# micromouse.net
KiCad netlist of a schematic drawn in EAGLE
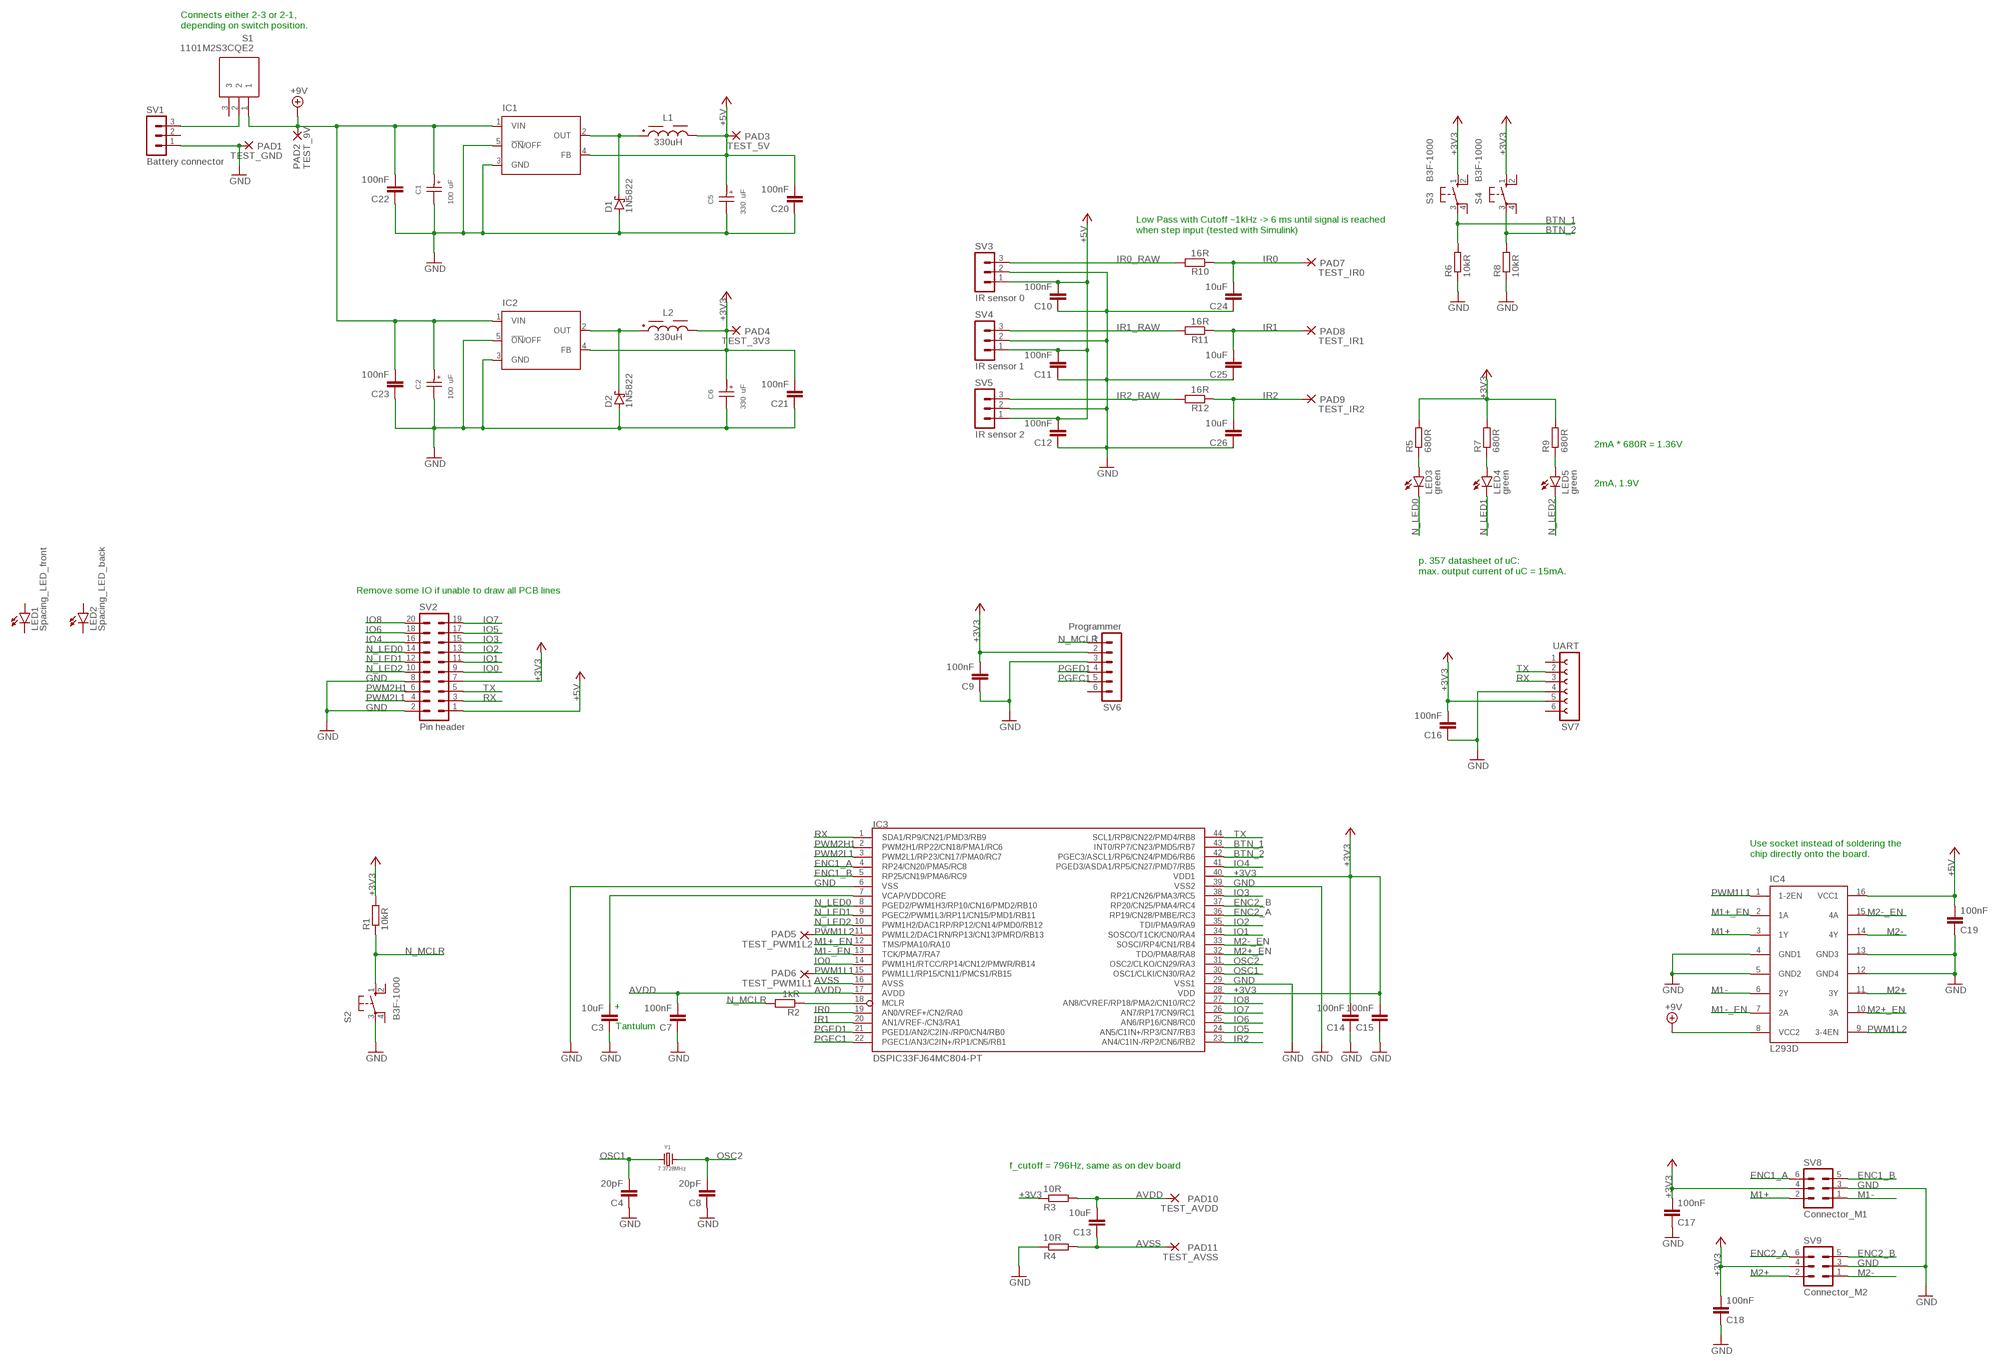
[diagram p0: schematic, sheet 1]

(export (version "E")
  (design (tool "Eeschema 10.0.6"))
  (components
    (comp (ref "C1")
      (value "100 uF")
      (footprint "eagle-import:WCAP-ATG5_5X11(DXL)")
      (libsource (lib "eagle-import") (part "WCAP-ATG5_5X11_860020272005"))
    )
    (comp (ref "C2")
      (value "100 uF")
      (footprint "eagle-import:WCAP-ATG5_5X11(DXL)")
      (libsource (lib "eagle-import") (part "WCAP-ATG5_5X11_860020272005"))
    )
    (comp (ref "C3")
      (value "10uF")
      (footprint "eagle-import:C0805")
      (libsource (lib "eagle-import") (part "C-EUC0805"))
    )
    (comp (ref "C4")
      (value "20pF")
      (footprint "eagle-import:C0805")
      (libsource (lib "eagle-import") (part "C-EUC0805"))
    )
    (comp (ref "C5")
      (value "330 uF")
      (footprint "eagle-import:WCAP-ATG5_6.3X11(DXL)")
      (libsource (lib "eagle-import") (part "WCAP-ATG5_6.3X11_860020273010"))
    )
    (comp (ref "C6")
      (value "330 uF")
      (footprint "eagle-import:WCAP-ATG5_6.3X11(DXL)")
      (libsource (lib "eagle-import") (part "WCAP-ATG5_6.3X11_860020273010"))
    )
    (comp (ref "C7")
      (value "100nF")
      (footprint "eagle-import:C0805")
      (libsource (lib "eagle-import") (part "C-EUC0805"))
    )
    (comp (ref "C8")
      (value "20pF")
      (footprint "eagle-import:C0805")
      (libsource (lib "eagle-import") (part "C-EUC0805"))
    )
    (comp (ref "C9")
      (value "100nF")
      (footprint "eagle-import:C0805")
      (libsource (lib "eagle-import") (part "C-EUC0805"))
    )
    (comp (ref "C10")
      (value "100nF")
      (footprint "eagle-import:C0805")
      (libsource (lib "eagle-import") (part "C-EUC0805"))
    )
    (comp (ref "C11")
      (value "100nF")
      (footprint "eagle-import:C0805")
      (libsource (lib "eagle-import") (part "C-EUC0805"))
    )
    (comp (ref "C12")
      (value "100nF")
      (footprint "eagle-import:C0805")
      (libsource (lib "eagle-import") (part "C-EUC0805"))
    )
    (comp (ref "C13")
      (value "10uF")
      (footprint "eagle-import:C0805")
      (libsource (lib "eagle-import") (part "C-EUC0805"))
    )
    (comp (ref "C14")
      (value "100nF")
      (footprint "eagle-import:C0805")
      (libsource (lib "eagle-import") (part "C-EUC0805"))
    )
    (comp (ref "C15")
      (value "100nF")
      (footprint "eagle-import:C0805")
      (libsource (lib "eagle-import") (part "C-EUC0805"))
    )
    (comp (ref "C16")
      (value "100nF")
      (footprint "eagle-import:C0805")
      (libsource (lib "eagle-import") (part "C-EUC0805"))
    )
    (comp (ref "C17")
      (value "100nF")
      (footprint "eagle-import:C0805")
      (libsource (lib "eagle-import") (part "C-EUC0805"))
    )
    (comp (ref "C18")
      (value "100nF")
      (footprint "eagle-import:C0805")
      (libsource (lib "eagle-import") (part "C-EUC0805"))
    )
    (comp (ref "C19")
      (value "100nF")
      (footprint "eagle-import:C0805")
      (libsource (lib "eagle-import") (part "C-EUC0805"))
    )
    (comp (ref "C20")
      (value "100nF")
      (footprint "eagle-import:C0805")
      (libsource (lib "eagle-import") (part "C-EUC0805"))
    )
    (comp (ref "C21")
      (value "100nF")
      (footprint "eagle-import:C0805")
      (libsource (lib "eagle-import") (part "C-EUC0805"))
    )
    (comp (ref "C22")
      (value "100nF")
      (footprint "eagle-import:C0805")
      (libsource (lib "eagle-import") (part "C-EUC0805"))
    )
    (comp (ref "C23")
      (value "100nF")
      (footprint "eagle-import:C0805")
      (libsource (lib "eagle-import") (part "C-EUC0805"))
    )
    (comp (ref "C24")
      (value "10uF")
      (footprint "eagle-import:C0805")
      (libsource (lib "eagle-import") (part "C-EUC0805"))
    )
    (comp (ref "C25")
      (value "10uF")
      (footprint "eagle-import:C0805")
      (libsource (lib "eagle-import") (part "C-EUC0805"))
    )
    (comp (ref "C26")
      (value "10uF")
      (footprint "eagle-import:C0805")
      (libsource (lib "eagle-import") (part "C-EUC0805"))
    )
    (comp (ref "D1")
      (value "1N5822")
      (footprint "eagle-import:DO35-10")
      (libsource (lib "eagle-import") (part "BAT19"))
    )
    (comp (ref "D2")
      (value "1N5822")
      (footprint "eagle-import:DO35-10")
      (libsource (lib "eagle-import") (part "BAT19"))
    )
    (comp (ref "IC1")
      (value "LM2575-5.0WU-(TR)")
      (footprint "eagle-import:TO263-5")
      (fields (field (name "MF") "NATIONAL SEMICONDUCTOR") (field (name "MPN") "LM2596S-ADJ/NOPB"))
      (libsource (lib "eagle-import") (part "LM2596S"))
    )
    (comp (ref "IC2")
      (value "LM2575-3.3WU-(TR)")
      (footprint "eagle-import:TO263-5")
      (fields (field (name "MF") "NATIONAL SEMICONDUCTOR") (field (name "MPN") "LM2596S-ADJ/NOPB"))
      (libsource (lib "eagle-import") (part "LM2596S"))
    )
    (comp (ref "IC3")
      (value "DSPIC33FJ64MC804-PT")
      (footprint "eagle-import:TQFP44")
      (libsource (lib "eagle-import") (part "DSPIC33FJ64MC804-PT"))
    )
    (comp (ref "IC4")
      (value "L293D")
      (footprint "eagle-import:DIL16")
      (libsource (lib "eagle-import") (part "L293D"))
    )
    (comp (ref "L1")
      (value "330uH")
      (footprint "eagle-import:WE-TIS_1111")
      (libsource (lib "eagle-import") (part "WE-TIS_1111_7447471331"))
    )
    (comp (ref "L2")
      (value "330uH")
      (footprint "eagle-import:WE-TIS_1111")
      (libsource (lib "eagle-import") (part "WE-TIS_1111_7447471331"))
    )
    (comp (ref "LED1")
      (value "Spacing_LED_front")
      (footprint "eagle-import:LED5MM")
      (libsource (lib "eagle-import") (part "LED5MM"))
    )
    (comp (ref "LED2")
      (value "Spacing_LED_back")
      (footprint "eagle-import:LED5MM")
      (libsource (lib "eagle-import") (part "LED5MM"))
    )
    (comp (ref "LED3")
      (value "green")
      (footprint "eagle-import:CHIP-LED0805")
      (libsource (lib "eagle-import") (part "LEDCHIP-LED0805"))
    )
    (comp (ref "LED4")
      (value "green")
      (footprint "eagle-import:CHIP-LED0805")
      (libsource (lib "eagle-import") (part "LEDCHIP-LED0805"))
    )
    (comp (ref "LED5")
      (value "green")
      (footprint "eagle-import:CHIP-LED0805")
      (libsource (lib "eagle-import") (part "LEDCHIP-LED0805"))
    )
    (comp (ref "PAD1")
      (value "TEST_GND")
      (footprint "eagle-import:3,17_1,3")
      (libsource (lib "eagle-import") (part "3,17/1,3"))
    )
    (comp (ref "PAD2")
      (value "TEST_9V")
      (footprint "eagle-import:3,17_1,3")
      (libsource (lib "eagle-import") (part "3,17/1,3"))
    )
    (comp (ref "PAD3")
      (value "TEST_5V")
      (footprint "eagle-import:3,17_1,3")
      (libsource (lib "eagle-import") (part "3,17/1,3"))
    )
    (comp (ref "PAD4")
      (value "TEST_3V3")
      (footprint "eagle-import:3,17_1,3")
      (libsource (lib "eagle-import") (part "3,17/1,3"))
    )
    (comp (ref "PAD5")
      (value "TEST_PWM1L2")
      (footprint "eagle-import:3,17_1,3")
      (libsource (lib "eagle-import") (part "3,17/1,3"))
    )
    (comp (ref "PAD6")
      (value "TEST_PWM1L1")
      (footprint "eagle-import:3,17_1,3")
      (libsource (lib "eagle-import") (part "3,17/1,3"))
    )
    (comp (ref "PAD7")
      (value "TEST_IR0")
      (footprint "eagle-import:3,17_1,3")
      (libsource (lib "eagle-import") (part "3,17/1,3"))
    )
    (comp (ref "PAD8")
      (value "TEST_IR1")
      (footprint "eagle-import:3,17_1,3")
      (libsource (lib "eagle-import") (part "3,17/1,3"))
    )
    (comp (ref "PAD9")
      (value "TEST_IR2")
      (footprint "eagle-import:3,17_1,3")
      (libsource (lib "eagle-import") (part "3,17/1,3"))
    )
    (comp (ref "PAD10")
      (value "TEST_AVDD")
      (footprint "eagle-import:3,17_1,3")
      (libsource (lib "eagle-import") (part "3,17/1,3"))
    )
    (comp (ref "PAD11")
      (value "TEST_AVSS")
      (footprint "eagle-import:3,17_1,3")
      (libsource (lib "eagle-import") (part "3,17/1,3"))
    )
    (comp (ref "R1")
      (value "10kR")
      (footprint "eagle-import:R0805")
      (libsource (lib "eagle-import") (part "R-EU_R0805"))
    )
    (comp (ref "R2")
      (value "1kR")
      (footprint "eagle-import:R0805")
      (libsource (lib "eagle-import") (part "R-EU_R0805"))
    )
    (comp (ref "R3")
      (value "10R")
      (footprint "eagle-import:R0805")
      (libsource (lib "eagle-import") (part "R-EU_R0805"))
    )
    (comp (ref "R4")
      (value "10R")
      (footprint "eagle-import:R0805")
      (libsource (lib "eagle-import") (part "R-EU_R0805"))
    )
    (comp (ref "R5")
      (value "680R")
      (footprint "eagle-import:R0805")
      (libsource (lib "eagle-import") (part "R-EU_R0805"))
    )
    (comp (ref "R6")
      (value "10kR")
      (footprint "eagle-import:R0805")
      (libsource (lib "eagle-import") (part "R-EU_R0805"))
    )
    (comp (ref "R7")
      (value "680R")
      (footprint "eagle-import:R0805")
      (libsource (lib "eagle-import") (part "R-EU_R0805"))
    )
    (comp (ref "R8")
      (value "10kR")
      (footprint "eagle-import:R0805")
      (libsource (lib "eagle-import") (part "R-EU_R0805"))
    )
    (comp (ref "R9")
      (value "680R")
      (footprint "eagle-import:R0805")
      (libsource (lib "eagle-import") (part "R-EU_R0805"))
    )
    (comp (ref "R10")
      (value "16R")
      (footprint "eagle-import:R0805")
      (libsource (lib "eagle-import") (part "R-EU_R0805"))
    )
    (comp (ref "R11")
      (value "16R")
      (footprint "eagle-import:R0805")
      (libsource (lib "eagle-import") (part "R-EU_R0805"))
    )
    (comp (ref "R12")
      (value "16R")
      (footprint "eagle-import:R0805")
      (libsource (lib "eagle-import") (part "R-EU_R0805"))
    )
    (comp (ref "S1")
      (value "1101M2S3CQE2")
      (footprint "eagle-import:1000-SERIES(SPDT)")
      (fields (field (name "MOUSER_PART_NUMBER") "611-1101M2S3CQE2"))
      (libsource (lib "eagle-import") (part "1101M2S3CQE2"))
    )
    (comp (ref "S2")
      (value "B3F-1000")
      (footprint "eagle-import:B3F-10XX")
      (libsource (lib "eagle-import") (part "10-XX"))
    )
    (comp (ref "S3")
      (value "B3F-1000")
      (footprint "eagle-import:B3F-10XX")
      (libsource (lib "eagle-import") (part "10-XX"))
    )
    (comp (ref "S4")
      (value "B3F-1000")
      (footprint "eagle-import:B3F-10XX")
      (libsource (lib "eagle-import") (part "10-XX"))
    )
    (comp (ref "SV1")
      (value "Battery connector")
      (footprint "eagle-import:MA03-1")
      (libsource (lib "eagle-import") (part "MA03-1"))
    )
    (comp (ref "SV2")
      (value "Pin header")
      (footprint "eagle-import:MA10-2")
      (libsource (lib "eagle-import") (part "MA10-2"))
    )
    (comp (ref "SV3")
      (value "IR sensor 0")
      (footprint "eagle-import:MA03-1")
      (libsource (lib "eagle-import") (part "MA03-1"))
    )
    (comp (ref "SV4")
      (value "IR sensor 1")
      (footprint "eagle-import:MA03-1")
      (libsource (lib "eagle-import") (part "MA03-1"))
    )
    (comp (ref "SV5")
      (value "IR sensor 2")
      (footprint "eagle-import:MA03-1")
      (libsource (lib "eagle-import") (part "MA03-1"))
    )
    (comp (ref "SV6")
      (value "Programmer")
      (footprint "eagle-import:MA06-1")
      (libsource (lib "eagle-import") (part "MA06-1"))
    )
    (comp (ref "SV7")
      (value "UART")
      (footprint "eagle-import:FE06")
      (libsource (lib "eagle-import") (part "FE06-1"))
    )
    (comp (ref "SV8")
      (value "Connector_M1")
      (footprint "eagle-import:ML6")
      (libsource (lib "eagle-import") (part "ML6"))
    )
    (comp (ref "SV9")
      (value "Connector_M2")
      (footprint "eagle-import:ML6")
      (libsource (lib "eagle-import") (part "ML6"))
    )
    (comp (ref "Y1")
      (value "7.3728MHz")
      (footprint "eagle-import:WE-XTAL_HC49_4H")
      (fields (field (name "TOLERANCE") "±30ppm"))
      (libsource (lib "eagle-import") (part "WE-XTAL_HC49/4H_830003335B"))
    )
  )
  (nets
    (net (code "1") (name "+3V3") (class "Default")
      (node (ref "C14") (pin "2") (pinfunction "2_2") (pintype "passive"))
      (node (ref "C15") (pin "2") (pinfunction "2_2") (pintype "passive"))
      (node (ref "C16") (pin "2") (pinfunction "2_2") (pintype "passive"))
      (node (ref "C17") (pin "2") (pinfunction "2_2") (pintype "passive"))
      (node (ref "C18") (pin "2") (pinfunction "2_2") (pintype "passive"))
      (node (ref "C21") (pin "2") (pinfunction "2_2") (pintype "passive"))
      (node (ref "C6") (pin "1") (pinfunction "+_1") (pintype "passive"))
      (node (ref "C9") (pin "2") (pinfunction "2_2") (pintype "passive"))
      (node (ref "IC2") (pin "4") (pinfunction "FB_4") (pintype "input"))
      (node (ref "IC3") (pin "28") (pinfunction "VDD_28") (pintype "power_in"))
      (node (ref "IC3") (pin "40") (pinfunction "VDD1_40") (pintype "power_in"))
      (node (ref "L2") (pin "2") (pinfunction "2_2") (pintype "passive"))
      (node (ref "PAD4") (pin "1") (pinfunction "P_1") (pintype "passive"))
      (node (ref "R1") (pin "2") (pinfunction "2_2") (pintype "passive"))
      (node (ref "R3") (pin "1") (pinfunction "1_1") (pintype "passive"))
      (node (ref "R5") (pin "2") (pinfunction "2_2") (pintype "passive"))
      (node (ref "R7") (pin "2") (pinfunction "2_2") (pintype "passive"))
      (node (ref "R9") (pin "2") (pinfunction "2_2") (pintype "passive"))
      (node (ref "S3") (pin "1") (pinfunction "S_1") (pintype "passive"))
      (node (ref "S4") (pin "1") (pinfunction "S_1") (pintype "passive"))
      (node (ref "SV2") (pin "7") (pinfunction "7_7") (pintype "passive"))
      (node (ref "SV6") (pin "2") (pinfunction "2_2") (pintype "passive"))
      (node (ref "SV7") (pin "5") (pinfunction "5_5") (pintype "passive"))
      (node (ref "SV8") (pin "4") (pinfunction "4_4") (pintype "passive"))
      (node (ref "SV9") (pin "4") (pinfunction "4_4") (pintype "passive"))
    )
    (net (code "2") (name "+5V") (class "Default")
      (node (ref "C10") (pin "2") (pinfunction "2_2") (pintype "passive"))
      (node (ref "C11") (pin "2") (pinfunction "2_2") (pintype "passive"))
      (node (ref "C12") (pin "2") (pinfunction "2_2") (pintype "passive"))
      (node (ref "C19") (pin "2") (pinfunction "2_2") (pintype "passive"))
      (node (ref "C20") (pin "2") (pinfunction "2_2") (pintype "passive"))
      (node (ref "C5") (pin "1") (pinfunction "+_1") (pintype "passive"))
      (node (ref "IC1") (pin "4") (pinfunction "FB_4") (pintype "input"))
      (node (ref "IC4") (pin "16") (pinfunction "VCC1_16") (pintype "power_in"))
      (node (ref "L1") (pin "2") (pinfunction "2_2") (pintype "passive"))
      (node (ref "PAD3") (pin "1") (pinfunction "P_1") (pintype "passive"))
      (node (ref "SV2") (pin "1") (pinfunction "1_1") (pintype "passive"))
      (node (ref "SV3") (pin "1") (pinfunction "1_1") (pintype "passive"))
      (node (ref "SV4") (pin "1") (pinfunction "1_1") (pintype "passive"))
      (node (ref "SV5") (pin "1") (pinfunction "1_1") (pintype "passive"))
    )
    (net (code "3") (name "+9V") (class "Default")
      (node (ref "C1") (pin "1") (pinfunction "+_1") (pintype "passive"))
      (node (ref "C2") (pin "1") (pinfunction "+_1") (pintype "passive"))
      (node (ref "C22") (pin "2") (pinfunction "2_2") (pintype "passive"))
      (node (ref "C23") (pin "2") (pinfunction "2_2") (pintype "passive"))
      (node (ref "IC1") (pin "1") (pinfunction "VIN_1") (pintype "input"))
      (node (ref "IC2") (pin "1") (pinfunction "VIN_1") (pintype "input"))
      (node (ref "IC4") (pin "8") (pinfunction "VCC2_8") (pintype "power_in"))
      (node (ref "PAD2") (pin "1") (pinfunction "P_1") (pintype "passive"))
      (node (ref "S1") (pin "1") (pinfunction "1_1") (pintype "bidirectional"))
    )
    (net (code "4") (name "/AVDD") (class "Default")
      (node (ref "C13") (pin "2") (pinfunction "2_2") (pintype "passive"))
      (node (ref "C7") (pin "2") (pinfunction "2_2") (pintype "passive"))
      (node (ref "IC3") (pin "17") (pinfunction "AVDD_17") (pintype "power_in"))
      (node (ref "PAD10") (pin "1") (pinfunction "P_1") (pintype "passive"))
      (node (ref "R3") (pin "2") (pinfunction "2_2") (pintype "passive"))
    )
    (net (code "5") (name "/AVSS") (class "Default")
      (node (ref "C13") (pin "1") (pinfunction "1_1") (pintype "passive"))
      (node (ref "IC3") (pin "16") (pinfunction "AVSS_16") (pintype "power_in"))
      (node (ref "PAD11") (pin "1") (pinfunction "P_1") (pintype "passive"))
      (node (ref "R4") (pin "2") (pinfunction "2_2") (pintype "passive"))
    )
    (net (code "6") (name "/BTN_1") (class "Default")
      (node (ref "IC3") (pin "43") (pinfunction "INT0/RP7/CN23/PMD5/RB7_43") (pintype "bidirectional"))
      (node (ref "R6") (pin "2") (pinfunction "2_2") (pintype "passive"))
      (node (ref "S3") (pin "3") (pinfunction "P_3") (pintype "passive"))
    )
    (net (code "7") (name "/BTN_2") (class "Default")
      (node (ref "IC3") (pin "42") (pinfunction "PGEC3/ASCL1/RP6/CN24/PMD6/RB6_42") (pintype "bidirectional"))
      (node (ref "R8") (pin "2") (pinfunction "2_2") (pintype "passive"))
      (node (ref "S4") (pin "3") (pinfunction "P_3") (pintype "passive"))
    )
    (net (code "8") (name "/ENC1_A") (class "Default")
      (node (ref "IC3") (pin "4") (pinfunction "RP24/CN20/PMA5/RC8_4") (pintype "bidirectional"))
      (node (ref "SV8") (pin "6") (pinfunction "6_6") (pintype "passive"))
    )
    (net (code "9") (name "/ENC1_B") (class "Default")
      (node (ref "IC3") (pin "5") (pinfunction "RP25/CN19/PMA6/RC9_5") (pintype "bidirectional"))
      (node (ref "SV8") (pin "5") (pinfunction "5_5") (pintype "passive"))
    )
    (net (code "10") (name "/ENC2_A") (class "Default")
      (node (ref "IC3") (pin "36") (pinfunction "RP19/CN28/PMBE/RC3_36") (pintype "bidirectional"))
      (node (ref "SV9") (pin "6") (pinfunction "6_6") (pintype "passive"))
    )
    (net (code "11") (name "/ENC2_B") (class "Default")
      (node (ref "IC3") (pin "37") (pinfunction "RP20/CN25/PMA4/RC4_37") (pintype "bidirectional"))
      (node (ref "SV9") (pin "5") (pinfunction "5_5") (pintype "passive"))
    )
    (net (code "12") (name "/IO0") (class "Default")
      (node (ref "IC3") (pin "14") (pinfunction "PWM1H1/RTCC/RP14/CN12/PMWR/RB14_14") (pintype "bidirectional"))
      (node (ref "SV2") (pin "9") (pinfunction "9_9") (pintype "passive"))
    )
    (net (code "13") (name "/IO1") (class "Default")
      (node (ref "IC3") (pin "34") (pinfunction "SOSCO/T1CK/CN0/RA4_34") (pintype "bidirectional"))
      (node (ref "SV2") (pin "11") (pinfunction "11_11") (pintype "passive"))
    )
    (net (code "14") (name "/IO2") (class "Default")
      (node (ref "IC3") (pin "35") (pinfunction "TDI/PMA9/RA9_35") (pintype "bidirectional"))
      (node (ref "SV2") (pin "13") (pinfunction "13_13") (pintype "passive"))
    )
    (net (code "15") (name "/IO3") (class "Default")
      (node (ref "IC3") (pin "38") (pinfunction "RP21/CN26/PMA3/RC5_38") (pintype "bidirectional"))
      (node (ref "SV2") (pin "15") (pinfunction "15_15") (pintype "passive"))
    )
    (net (code "16") (name "/IO4") (class "Default")
      (node (ref "IC3") (pin "41") (pinfunction "PGED3/ASDA1/RP5/CN27/PMD7/RB5_41") (pintype "bidirectional"))
      (node (ref "SV2") (pin "16") (pinfunction "16_16") (pintype "passive"))
    )
    (net (code "17") (name "/IO5") (class "Default")
      (node (ref "IC3") (pin "24") (pinfunction "AN5/C1IN+/RP3/CN7/RB3_24") (pintype "bidirectional"))
      (node (ref "SV2") (pin "17") (pinfunction "17_17") (pintype "passive"))
    )
    (net (code "18") (name "/IO6") (class "Default")
      (node (ref "IC3") (pin "25") (pinfunction "AN6/RP16/CN8/RC0_25") (pintype "bidirectional"))
      (node (ref "SV2") (pin "18") (pinfunction "18_18") (pintype "passive"))
    )
    (net (code "19") (name "/IO7") (class "Default")
      (node (ref "IC3") (pin "26") (pinfunction "AN7/RP17/CN9/RC1_26") (pintype "bidirectional"))
      (node (ref "SV2") (pin "19") (pinfunction "19_19") (pintype "passive"))
    )
    (net (code "20") (name "/IO8") (class "Default")
      (node (ref "IC3") (pin "27") (pinfunction "AN8/CVREF/RP18/PMA2/CN10/RC2_27") (pintype "bidirectional"))
      (node (ref "SV2") (pin "20") (pinfunction "20_20") (pintype "passive"))
    )
    (net (code "21") (name "/IR0") (class "Default")
      (node (ref "C24") (pin "2") (pinfunction "2_2") (pintype "passive"))
      (node (ref "IC3") (pin "19") (pinfunction "AN0/VREF+/CN2/RA0_19") (pintype "bidirectional"))
      (node (ref "PAD7") (pin "1") (pinfunction "P_1") (pintype "passive"))
      (node (ref "R10") (pin "1") (pinfunction "1_1") (pintype "passive"))
    )
    (net (code "22") (name "/IR0_RAW") (class "Default")
      (node (ref "R10") (pin "2") (pinfunction "2_2") (pintype "passive"))
      (node (ref "SV3") (pin "3") (pinfunction "3_3") (pintype "passive"))
    )
    (net (code "23") (name "/IR1") (class "Default")
      (node (ref "C25") (pin "2") (pinfunction "2_2") (pintype "passive"))
      (node (ref "IC3") (pin "20") (pinfunction "AN1/VREF-/CN3/RA1_20") (pintype "bidirectional"))
      (node (ref "PAD8") (pin "1") (pinfunction "P_1") (pintype "passive"))
      (node (ref "R11") (pin "1") (pinfunction "1_1") (pintype "passive"))
    )
    (net (code "24") (name "/IR1_RAW") (class "Default")
      (node (ref "R11") (pin "2") (pinfunction "2_2") (pintype "passive"))
      (node (ref "SV4") (pin "3") (pinfunction "3_3") (pintype "passive"))
    )
    (net (code "25") (name "/IR2") (class "Default")
      (node (ref "C26") (pin "2") (pinfunction "2_2") (pintype "passive"))
      (node (ref "IC3") (pin "23") (pinfunction "AN4/C1IN-/RP2/CN6/RB2_23") (pintype "bidirectional"))
      (node (ref "PAD9") (pin "1") (pinfunction "P_1") (pintype "passive"))
      (node (ref "R12") (pin "1") (pinfunction "1_1") (pintype "passive"))
    )
    (net (code "26") (name "/IR2_RAW") (class "Default")
      (node (ref "R12") (pin "2") (pinfunction "2_2") (pintype "passive"))
      (node (ref "SV5") (pin "3") (pinfunction "3_3") (pintype "passive"))
    )
    (net (code "27") (name "/M1+") (class "Default")
      (node (ref "IC4") (pin "3") (pinfunction "1Y_3") (pintype "output"))
      (node (ref "SV8") (pin "2") (pinfunction "2_2") (pintype "passive"))
    )
    (net (code "28") (name "/M1+_EN") (class "Default")
      (node (ref "IC3") (pin "12") (pinfunction "TMS/PMA10/RA10_12") (pintype "bidirectional"))
      (node (ref "IC4") (pin "2") (pinfunction "1A_2") (pintype "input"))
    )
    (net (code "29") (name "/M1-") (class "Default")
      (node (ref "IC4") (pin "6") (pinfunction "2Y_6") (pintype "output"))
      (node (ref "SV8") (pin "1") (pinfunction "1_1") (pintype "passive"))
    )
    (net (code "30") (name "/M1-_EN") (class "Default")
      (node (ref "IC3") (pin "13") (pinfunction "TCK/PMA7/RA7_13") (pintype "bidirectional"))
      (node (ref "IC4") (pin "7") (pinfunction "2A_7") (pintype "input"))
    )
    (net (code "31") (name "/M2+") (class "Default")
      (node (ref "IC4") (pin "11") (pinfunction "3Y_11") (pintype "output"))
      (node (ref "SV9") (pin "2") (pinfunction "2_2") (pintype "passive"))
    )
    (net (code "32") (name "/M2+_EN") (class "Default")
      (node (ref "IC3") (pin "32") (pinfunction "TDO/PMA8/RA8_32") (pintype "bidirectional"))
      (node (ref "IC4") (pin "10") (pinfunction "3A_10") (pintype "input"))
    )
    (net (code "33") (name "/M2-") (class "Default")
      (node (ref "IC4") (pin "14") (pinfunction "4Y_14") (pintype "output"))
      (node (ref "SV9") (pin "1") (pinfunction "1_1") (pintype "passive"))
    )
    (net (code "34") (name "/M2-_EN") (class "Default")
      (node (ref "IC3") (pin "33") (pinfunction "SOSCI/RP4/CN1/RB4_33") (pintype "bidirectional"))
      (node (ref "IC4") (pin "15") (pinfunction "4A_15") (pintype "input"))
    )
    (net (code "35") (name "/N_LED0") (class "Default")
      (node (ref "IC3") (pin "8") (pinfunction "PGED2/PWM1H3/RP10/CN16/PMD2/RB10_8") (pintype "bidirectional"))
      (node (ref "LED3") (pin "C") (pinfunction "C_C") (pintype "passive"))
      (node (ref "SV2") (pin "14") (pinfunction "14_14") (pintype "passive"))
    )
    (net (code "36") (name "/N_LED1") (class "Default")
      (node (ref "IC3") (pin "9") (pinfunction "PGEC2/PWM1L3/RP11/CN15/PMD1/RB11_9") (pintype "bidirectional"))
      (node (ref "LED4") (pin "C") (pinfunction "C_C") (pintype "passive"))
      (node (ref "SV2") (pin "12") (pinfunction "12_12") (pintype "passive"))
    )
    (net (code "37") (name "/N_LED2") (class "Default")
      (node (ref "IC3") (pin "10") (pinfunction "PWM1H2/DAC1RP/RP12/CN14/PMD0/RB12_10") (pintype "bidirectional"))
      (node (ref "LED5") (pin "C") (pinfunction "C_C") (pintype "passive"))
      (node (ref "SV2") (pin "10") (pinfunction "10_10") (pintype "passive"))
    )
    (net (code "38") (name "/N_MCLR") (class "Default")
      (node (ref "R1") (pin "1") (pinfunction "1_1") (pintype "passive"))
      (node (ref "R2") (pin "2") (pinfunction "2_2") (pintype "passive"))
      (node (ref "S2") (pin "1") (pinfunction "S_1") (pintype "passive"))
      (node (ref "SV6") (pin "1") (pinfunction "1_1") (pintype "passive"))
    )
    (net (code "39") (name "/OSC1") (class "Default")
      (node (ref "C4") (pin "2") (pinfunction "2_2") (pintype "passive"))
      (node (ref "IC3") (pin "30") (pinfunction "OSC1/CLKI/CN30/RA2_30") (pintype "bidirectional"))
      (node (ref "Y1") (pin "1") (pinfunction "1_1") (pintype "passive"))
    )
    (net (code "40") (name "/OSC2") (class "Default")
      (node (ref "C8") (pin "2") (pinfunction "2_2") (pintype "passive"))
      (node (ref "IC3") (pin "31") (pinfunction "OSC2/CLKO/CN29/RA3_31") (pintype "bidirectional"))
      (node (ref "Y1") (pin "2") (pinfunction "2_2") (pintype "passive"))
    )
    (net (code "41") (name "/PGEC1") (class "Default")
      (node (ref "IC3") (pin "22") (pinfunction "PGEC1/AN3/C2IN+/RP1/CN5/RB1_22") (pintype "bidirectional"))
      (node (ref "SV6") (pin "5") (pinfunction "5_5") (pintype "passive"))
    )
    (net (code "42") (name "/PGED1") (class "Default")
      (node (ref "IC3") (pin "21") (pinfunction "PGED1/AN2/C2IN-/RP0/CN4/RB0_21") (pintype "bidirectional"))
      (node (ref "SV6") (pin "4") (pinfunction "4_4") (pintype "passive"))
    )
    (net (code "43") (name "/PWM1L1") (class "Default")
      (node (ref "IC3") (pin "15") (pinfunction "PWM1L1/RP15/CN11/PMCS1/RB15_15") (pintype "bidirectional"))
      (node (ref "IC4") (pin "1") (pinfunction "1-2EN_1") (pintype "input"))
      (node (ref "PAD6") (pin "1") (pinfunction "P_1") (pintype "passive"))
    )
    (net (code "44") (name "/PWM1L2") (class "Default")
      (node (ref "IC3") (pin "11") (pinfunction "PWM1L2/DAC1RN/RP13/CN13/PMRD/RB13_11") (pintype "bidirectional"))
      (node (ref "IC4") (pin "9") (pinfunction "3-4EN_9") (pintype "input"))
      (node (ref "PAD5") (pin "1") (pinfunction "P_1") (pintype "passive"))
    )
    (net (code "45") (name "/PWM2H1") (class "Default")
      (node (ref "IC3") (pin "2") (pinfunction "PWM2H1/RP22/CN18/PMA1/RC6_2") (pintype "bidirectional"))
      (node (ref "SV2") (pin "6") (pinfunction "6_6") (pintype "passive"))
    )
    (net (code "46") (name "/PWM2L1") (class "Default")
      (node (ref "IC3") (pin "3") (pinfunction "PWM2L1/RP23/CN17/PMA0/RC7_3") (pintype "bidirectional"))
      (node (ref "SV2") (pin "4") (pinfunction "4_4") (pintype "passive"))
    )
    (net (code "47") (name "/RX") (class "Default")
      (node (ref "IC3") (pin "1") (pinfunction "SDA1/RP9/CN21/PMD3/RB9_1") (pintype "bidirectional"))
      (node (ref "SV2") (pin "3") (pinfunction "3_3") (pintype "passive"))
      (node (ref "SV7") (pin "3") (pinfunction "3_3") (pintype "passive"))
    )
    (net (code "48") (name "/TX") (class "Default")
      (node (ref "IC3") (pin "44") (pinfunction "SCL1/RP8/CN22/PMD4/RB8_44") (pintype "bidirectional"))
      (node (ref "SV2") (pin "5") (pinfunction "5_5") (pintype "passive"))
      (node (ref "SV7") (pin "2") (pinfunction "2_2") (pintype "passive"))
    )
    (net (code "49") (name "GND") (class "Default")
      (node (ref "C1") (pin "2") (pinfunction "-_2") (pintype "passive"))
      (node (ref "C10") (pin "1") (pinfunction "1_1") (pintype "passive"))
      (node (ref "C11") (pin "1") (pinfunction "1_1") (pintype "passive"))
      (node (ref "C12") (pin "1") (pinfunction "1_1") (pintype "passive"))
      (node (ref "C14") (pin "1") (pinfunction "1_1") (pintype "passive"))
      (node (ref "C15") (pin "1") (pinfunction "1_1") (pintype "passive"))
      (node (ref "C16") (pin "1") (pinfunction "1_1") (pintype "passive"))
      (node (ref "C17") (pin "1") (pinfunction "1_1") (pintype "passive"))
      (node (ref "C18") (pin "1") (pinfunction "1_1") (pintype "passive"))
      (node (ref "C19") (pin "1") (pinfunction "1_1") (pintype "passive"))
      (node (ref "C2") (pin "2") (pinfunction "-_2") (pintype "passive"))
      (node (ref "C20") (pin "1") (pinfunction "1_1") (pintype "passive"))
      (node (ref "C21") (pin "1") (pinfunction "1_1") (pintype "passive"))
      (node (ref "C22") (pin "1") (pinfunction "1_1") (pintype "passive"))
      (node (ref "C23") (pin "1") (pinfunction "1_1") (pintype "passive"))
      (node (ref "C24") (pin "1") (pinfunction "1_1") (pintype "passive"))
      (node (ref "C25") (pin "1") (pinfunction "1_1") (pintype "passive"))
      (node (ref "C26") (pin "1") (pinfunction "1_1") (pintype "passive"))
      (node (ref "C3") (pin "1") (pinfunction "1_1") (pintype "passive"))
      (node (ref "C4") (pin "1") (pinfunction "1_1") (pintype "passive"))
      (node (ref "C5") (pin "2") (pinfunction "-_2") (pintype "passive"))
      (node (ref "C6") (pin "2") (pinfunction "-_2") (pintype "passive"))
      (node (ref "C7") (pin "1") (pinfunction "1_1") (pintype "passive"))
      (node (ref "C8") (pin "1") (pinfunction "1_1") (pintype "passive"))
      (node (ref "C9") (pin "1") (pinfunction "1_1") (pintype "passive"))
      (node (ref "D1") (pin "A") (pinfunction "A_A") (pintype "passive"))
      (node (ref "D2") (pin "A") (pinfunction "A_A") (pintype "passive"))
      (node (ref "IC1") (pin "3") (pinfunction "GND_3") (pintype "power_in"))
      (node (ref "IC1") (pin "5") (pinfunction "~{ON}/OFF_5") (pintype "input"))
      (node (ref "IC2") (pin "3") (pinfunction "GND_3") (pintype "power_in"))
      (node (ref "IC2") (pin "5") (pinfunction "~{ON}/OFF_5") (pintype "input"))
      (node (ref "IC3") (pin "29") (pinfunction "VSS1_29") (pintype "power_in"))
      (node (ref "IC3") (pin "39") (pinfunction "VSS2_39") (pintype "power_in"))
      (node (ref "IC3") (pin "6") (pinfunction "VSS_6") (pintype "power_in"))
      (node (ref "IC4") (pin "12") (pinfunction "GND4_12") (pintype "power_in"))
      (node (ref "IC4") (pin "13") (pinfunction "GND3_13") (pintype "power_in"))
      (node (ref "IC4") (pin "4") (pinfunction "GND1_4") (pintype "power_in"))
      (node (ref "IC4") (pin "5") (pinfunction "GND2_5") (pintype "power_in"))
      (node (ref "PAD1") (pin "1") (pinfunction "P_1") (pintype "passive"))
      (node (ref "R4") (pin "1") (pinfunction "1_1") (pintype "passive"))
      (node (ref "R6") (pin "1") (pinfunction "1_1") (pintype "passive"))
      (node (ref "R8") (pin "1") (pinfunction "1_1") (pintype "passive"))
      (node (ref "S2") (pin "3") (pinfunction "P_3") (pintype "passive"))
      (node (ref "SV1") (pin "1") (pinfunction "1_1") (pintype "passive"))
      (node (ref "SV2") (pin "2") (pinfunction "2_2") (pintype "passive"))
      (node (ref "SV2") (pin "8") (pinfunction "8_8") (pintype "passive"))
      (node (ref "SV3") (pin "2") (pinfunction "2_2") (pintype "passive"))
      (node (ref "SV4") (pin "2") (pinfunction "2_2") (pintype "passive"))
      (node (ref "SV5") (pin "2") (pinfunction "2_2") (pintype "passive"))
      (node (ref "SV6") (pin "3") (pinfunction "3_3") (pintype "passive"))
      (node (ref "SV7") (pin "4") (pinfunction "4_4") (pintype "passive"))
      (node (ref "SV8") (pin "3") (pinfunction "3_3") (pintype "passive"))
      (node (ref "SV9") (pin "3") (pinfunction "3_3") (pintype "passive"))
    )
    (net (code "50") (name "Net-(IC1-OUT)") (class "Default")
      (node (ref "D1") (pin "C") (pinfunction "C_C") (pintype "passive"))
      (node (ref "IC1") (pin "2") (pinfunction "OUT_2") (pintype "output"))
      (node (ref "L1") (pin "1") (pinfunction "1_1") (pintype "passive"))
    )
    (net (code "51") (name "Net-(IC2-OUT)") (class "Default")
      (node (ref "D2") (pin "C") (pinfunction "C_C") (pintype "passive"))
      (node (ref "IC2") (pin "2") (pinfunction "OUT_2") (pintype "output"))
      (node (ref "L2") (pin "1") (pinfunction "1_1") (pintype "passive"))
    )
    (net (code "52") (name "Net-(IC3-MCLR)") (class "Default")
      (node (ref "IC3") (pin "18") (pinfunction "MCLR_18") (pintype "input"))
      (node (ref "R2") (pin "1") (pinfunction "1_1") (pintype "passive"))
    )
    (net (code "53") (name "Net-(IC3-VCAP{slash}VDDCORE)") (class "Default")
      (node (ref "C3") (pin "2") (pinfunction "2_2") (pintype "passive"))
      (node (ref "IC3") (pin "7") (pinfunction "VCAP/VDDCORE_7") (pintype "power_in"))
    )
    (net (code "54") (name "Net-(LED3-PadA)") (class "Default")
      (node (ref "LED3") (pin "A") (pinfunction "A_A") (pintype "passive"))
      (node (ref "R5") (pin "1") (pinfunction "1_1") (pintype "passive"))
    )
    (net (code "55") (name "Net-(LED4-PadA)") (class "Default")
      (node (ref "LED4") (pin "A") (pinfunction "A_A") (pintype "passive"))
      (node (ref "R7") (pin "1") (pinfunction "1_1") (pintype "passive"))
    )
    (net (code "56") (name "Net-(LED5-PadA)") (class "Default")
      (node (ref "LED5") (pin "A") (pinfunction "A_A") (pintype "passive"))
      (node (ref "R9") (pin "1") (pinfunction "1_1") (pintype "passive"))
    )
    (net (code "57") (name "Net-(S1-Pad2)") (class "Default")
      (node (ref "S1") (pin "2") (pinfunction "2_2") (pintype "bidirectional"))
      (node (ref "SV1") (pin "3") (pinfunction "3_3") (pintype "passive"))
    )
    (net (code "58") (name "unconnected-(LED1-C-PadK)") (class "Default")
      (node (ref "LED1") (pin "K") (pinfunction "C_K") (pintype "passive"))
    )
    (net (code "59") (name "unconnected-(LED1-PadA)") (class "Default")
      (node (ref "LED1") (pin "A") (pinfunction "A_A") (pintype "passive"))
    )
    (net (code "60") (name "unconnected-(LED2-C-PadK)") (class "Default")
      (node (ref "LED2") (pin "K") (pinfunction "C_K") (pintype "passive"))
    )
    (net (code "61") (name "unconnected-(LED2-PadA)") (class "Default")
      (node (ref "LED2") (pin "A") (pinfunction "A_A") (pintype "passive"))
    )
    (net (code "62") (name "unconnected-(S1-Pad3)") (class "Default")
      (node (ref "S1") (pin "3") (pinfunction "3_3") (pintype "bidirectional"))
    )
    (net (code "63") (name "unconnected-(S2-P1-Pad4)") (class "Default")
      (node (ref "S2") (pin "4") (pinfunction "P1_4") (pintype "passive"))
    )
    (net (code "64") (name "unconnected-(S2-S1-Pad2)") (class "Default")
      (node (ref "S2") (pin "2") (pinfunction "S1_2") (pintype "passive"))
    )
    (net (code "65") (name "unconnected-(S3-P1-Pad4)") (class "Default")
      (node (ref "S3") (pin "4") (pinfunction "P1_4") (pintype "passive"))
    )
    (net (code "66") (name "unconnected-(S3-S1-Pad2)") (class "Default")
      (node (ref "S3") (pin "2") (pinfunction "S1_2") (pintype "passive"))
    )
    (net (code "67") (name "unconnected-(S4-P1-Pad4)") (class "Default")
      (node (ref "S4") (pin "4") (pinfunction "P1_4") (pintype "passive"))
    )
    (net (code "68") (name "unconnected-(S4-S1-Pad2)") (class "Default")
      (node (ref "S4") (pin "2") (pinfunction "S1_2") (pintype "passive"))
    )
    (net (code "69") (name "unconnected-(SV1-Pad2)") (class "Default")
      (node (ref "SV1") (pin "2") (pinfunction "2_2") (pintype "passive"))
    )
    (net (code "70") (name "unconnected-(SV6-Pad6)") (class "Default")
      (node (ref "SV6") (pin "6") (pinfunction "6_6") (pintype "passive"))
    )
    (net (code "71") (name "unconnected-(SV7-Pad1)") (class "Default")
      (node (ref "SV7") (pin "1") (pinfunction "1_1") (pintype "passive"))
    )
    (net (code "72") (name "unconnected-(SV7-Pad6)") (class "Default")
      (node (ref "SV7") (pin "6") (pinfunction "6_6") (pintype "passive"))
    )
  )
)
